# LB_w19_SPLIT_IN-v03_rev2_2_-OHW.net
KiCad netlist of a schematic drawn in EAGLE
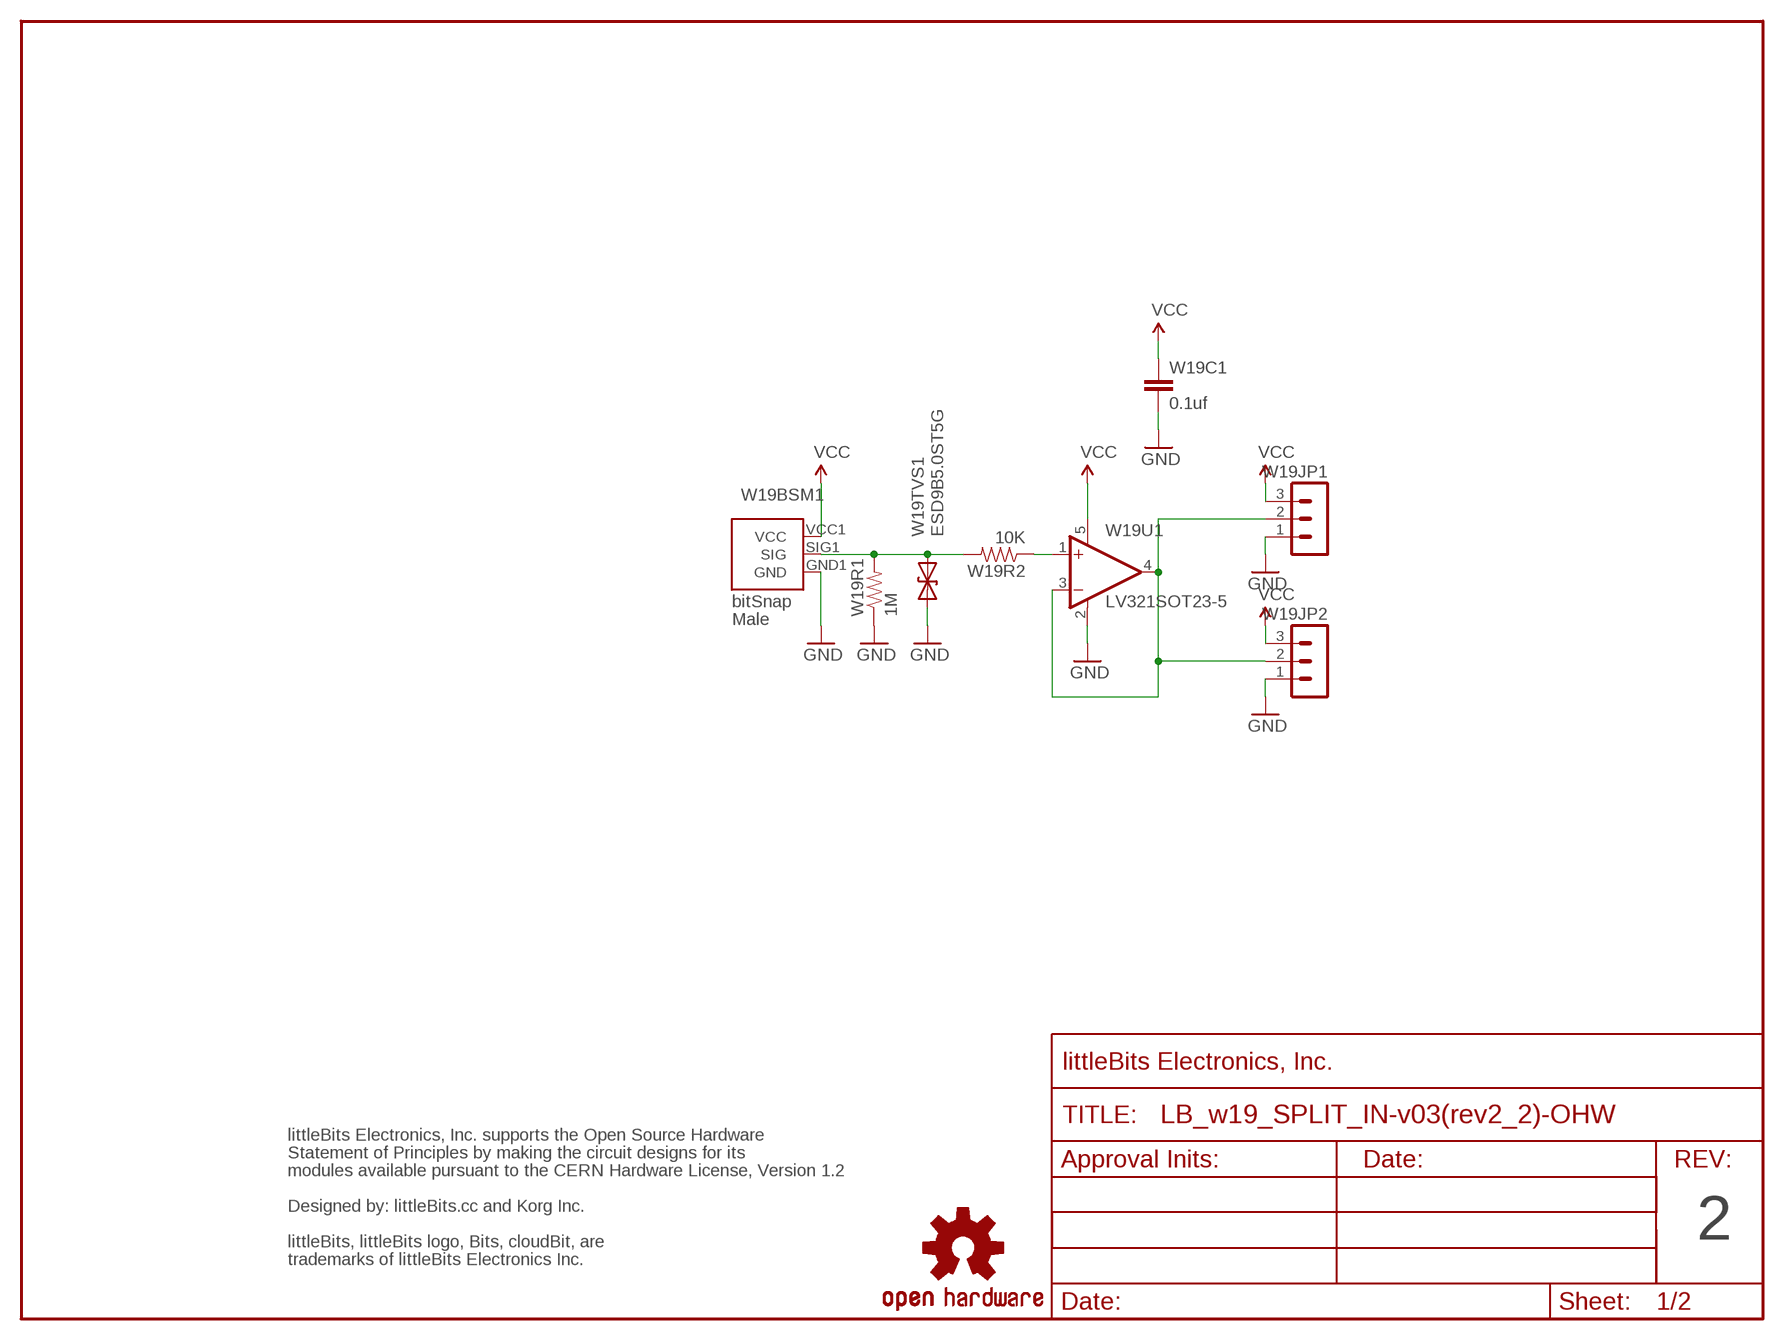
[diagram p0: schematic, sheet 1]

(export (version "E")
  (design (tool "Eeschema 10.0.6"))
  (components
    (comp (ref "FRAME1")
      (value "FRAME-LETTER-OHWOHW")
      (footprint "eagle-import:FABDWG01-OHW")
      (libsource (lib "eagle-import") (part "FRAME-LETTER-OHWOHW"))
    )
    (comp (ref "U$1")
      (value "OSHWCREDIT-KORG")
      (footprint "eagle-import:OSHWCREDIT-KORG")
      (libsource (lib "eagle-import") (part "OSHWCREDIT-KORG"))
    )
    (comp (ref "U$3")
      (value "OSHW-LOGOL")
      (footprint "eagle-import:OSHW-LOGO-L")
      (libsource (lib "eagle-import") (part "OSHW-LOGOL"))
    )
    (comp (ref "W19BSM1")
      (value "BITSNAP_V03_MALE")
      (footprint "eagle-import:BITSNAP_V03_MALE")
      (libsource (lib "eagle-import") (part "BITSNAP_V03_MALE"))
    )
    (comp (ref "W19C1")
      (value "0.1uf")
      (footprint "eagle-import:CAP-0603")
      (libsource (lib "eagle-import") (part "CAPCAP-0603"))
    )
    (comp (ref "W19JP1")
      (value "MA03-1SMD")
      (footprint "eagle-import:1X03-1MM-RA")
      (libsource (lib "eagle-import") (part "MA03-1SMD"))
    )
    (comp (ref "W19JP2")
      (value "MA03-1SMD")
      (footprint "eagle-import:1X03-1MM-RA")
      (libsource (lib "eagle-import") (part "MA03-1SMD"))
    )
    (comp (ref "W19R1")
      (value "1M")
      (footprint "eagle-import:RES-0603")
      (libsource (lib "eagle-import") (part "RESISTOR0603"))
    )
    (comp (ref "W19R2")
      (value "10K")
      (footprint "eagle-import:RES-0603")
      (libsource (lib "eagle-import") (part "RESISTOR0603"))
    )
    (comp (ref "W19TVS1")
      (value "ESD9B5.0ST5G")
      (footprint "eagle-import:SOD-923")
      (libsource (lib "eagle-import") (part "DIODE-TVSSOD-923"))
    )
    (comp (ref "W19U1")
      (value "LV321SOT23-5")
      (footprint "eagle-import:SOT23-5")
      (libsource (lib "eagle-import") (part "LV321SOT23-5"))
    )
  )
  (nets
    (net (code "1") (name "GND") (class "Default")
      (node (ref "W19BSM1") (pin "GND1") (pinfunction "GND_GND1") (pintype "bidirectional"))
      (node (ref "W19C1") (pin "2") (pinfunction "2_2") (pintype "passive"))
      (node (ref "W19JP1") (pin "1") (pinfunction "1_1") (pintype "passive"))
      (node (ref "W19JP2") (pin "1") (pinfunction "1_1") (pintype "passive"))
      (node (ref "W19R1") (pin "1") (pinfunction "1_1") (pintype "passive"))
      (node (ref "W19TVS1") (pin "1") (pinfunction "A_1") (pintype "passive"))
      (node (ref "W19U1") (pin "2") (pinfunction "V-_2") (pintype "power_in"))
    )
    (net (code "2") (name "Net-(W19BSM1-SIG)") (class "Default")
      (node (ref "W19BSM1") (pin "SIG1") (pinfunction "SIG_SIG1") (pintype "bidirectional"))
      (node (ref "W19R1") (pin "2") (pinfunction "2_2") (pintype "passive"))
      (node (ref "W19R2") (pin "2") (pinfunction "2_2") (pintype "passive"))
      (node (ref "W19TVS1") (pin "2") (pinfunction "C_2") (pintype "passive"))
    )
    (net (code "3") (name "Net-(W19U1-+IN)") (class "Default")
      (node (ref "W19R2") (pin "1") (pinfunction "1_1") (pintype "passive"))
      (node (ref "W19U1") (pin "1") (pinfunction "+IN_1") (pintype "input"))
    )
    (net (code "4") (name "Net-(W19U1--IN)") (class "Default")
      (node (ref "W19JP1") (pin "2") (pinfunction "2_2") (pintype "passive"))
      (node (ref "W19JP2") (pin "2") (pinfunction "2_2") (pintype "passive"))
      (node (ref "W19U1") (pin "3") (pinfunction "-IN_3") (pintype "input"))
      (node (ref "W19U1") (pin "4") (pinfunction "OUT_4") (pintype "output"))
    )
    (net (code "5") (name "VCC") (class "Default")
      (node (ref "W19BSM1") (pin "VCC1") (pinfunction "VCC_VCC1") (pintype "bidirectional"))
      (node (ref "W19C1") (pin "1") (pinfunction "1_1") (pintype "passive"))
      (node (ref "W19JP1") (pin "3") (pinfunction "3_3") (pintype "passive"))
      (node (ref "W19JP2") (pin "3") (pinfunction "3_3") (pintype "passive"))
      (node (ref "W19U1") (pin "5") (pinfunction "V+_5") (pintype "power_in"))
    )
  )
)
